# BoxVersion_Taster_v1.net
KiCad netlist of a schematic drawn in EAGLE
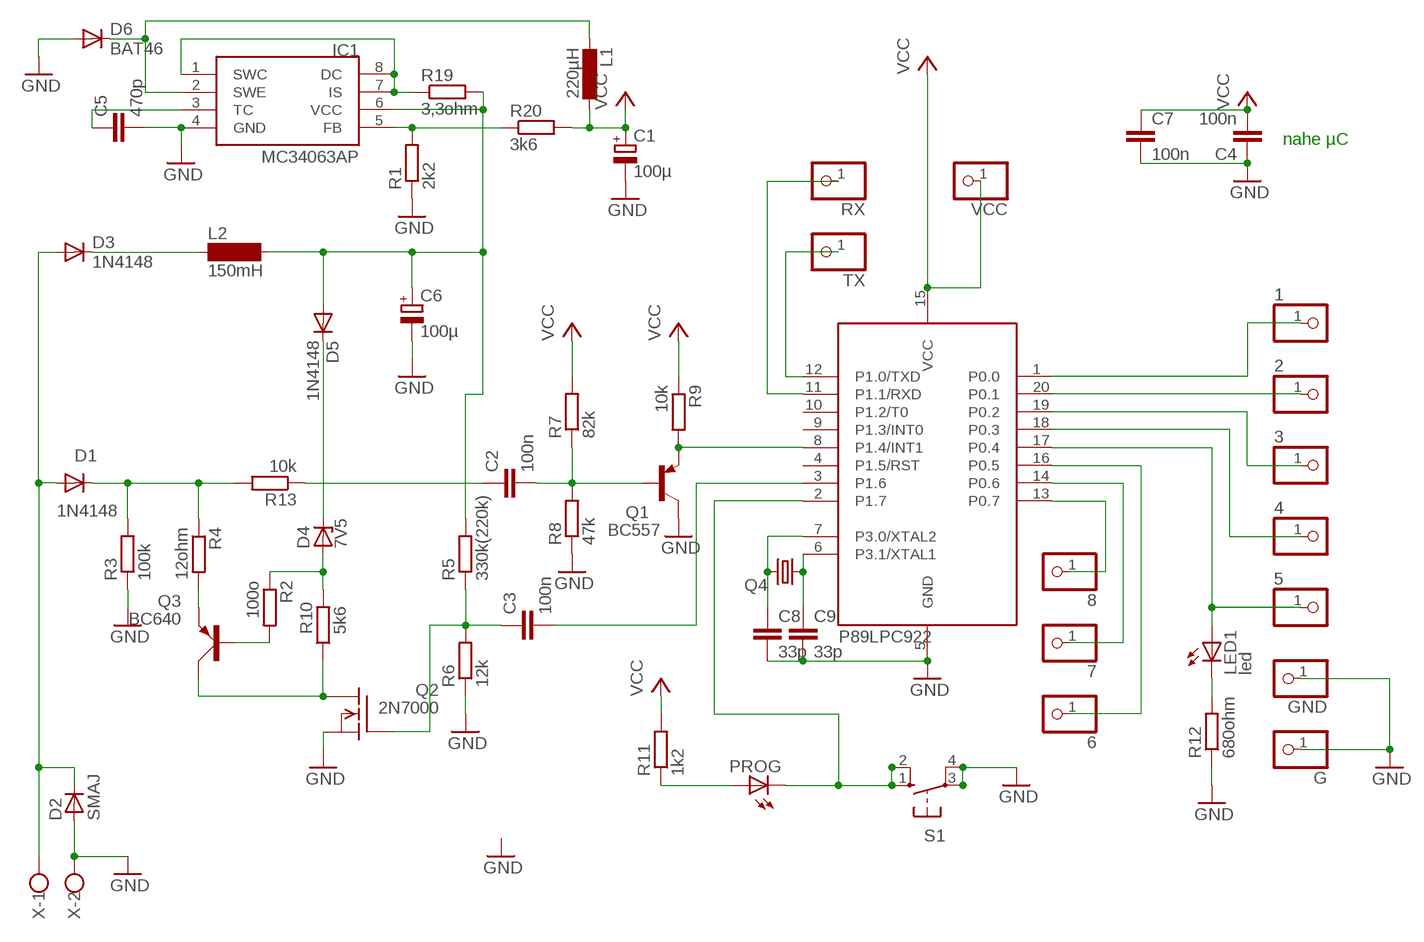
[diagram p0: schematic, sheet 1]

(export (version "E")
  (design (tool "Eeschema 10.0.6"))
  (components
    (comp (ref "1")
      (value "PINHD-1X1")
      (footprint "eagle-import:1X01")
      (libsource (lib "eagle-import") (part "PINHD-1X1"))
    )
    (comp (ref "2")
      (value "PINHD-1X1")
      (footprint "eagle-import:1X01")
      (libsource (lib "eagle-import") (part "PINHD-1X1"))
    )
    (comp (ref "3")
      (value "PINHD-1X1")
      (footprint "eagle-import:1X01")
      (libsource (lib "eagle-import") (part "PINHD-1X1"))
    )
    (comp (ref "4")
      (value "PINHD-1X1")
      (footprint "eagle-import:1X01")
      (libsource (lib "eagle-import") (part "PINHD-1X1"))
    )
    (comp (ref "5")
      (value "PINHD-1X1")
      (footprint "eagle-import:1X01")
      (libsource (lib "eagle-import") (part "PINHD-1X1"))
    )
    (comp (ref "6")
      (value "PINHD-1X1")
      (footprint "eagle-import:1X01")
      (libsource (lib "eagle-import") (part "PINHD-1X1"))
    )
    (comp (ref "7")
      (value "PINHD-1X1")
      (footprint "eagle-import:1X01")
      (libsource (lib "eagle-import") (part "PINHD-1X1"))
    )
    (comp (ref "8")
      (value "PINHD-1X1")
      (footprint "eagle-import:1X01")
      (libsource (lib "eagle-import") (part "PINHD-1X1"))
    )
    (comp (ref "C1")
      (value "100µ")
      (footprint "eagle-import:E5-5")
      (libsource (lib "eagle-import") (part "CPOL-EUE5-5"))
    )
    (comp (ref "C2")
      (value "100n")
      (footprint "eagle-import:C050-024X044")
      (libsource (lib "eagle-import") (part "C-EU050-024X044"))
    )
    (comp (ref "C3")
      (value "100n")
      (footprint "eagle-import:C050-024X044")
      (libsource (lib "eagle-import") (part "C-EU050-024X044"))
    )
    (comp (ref "C4")
      (value "100n")
      (footprint "eagle-import:C050-024X044")
      (libsource (lib "eagle-import") (part "C-EU050-024X044"))
    )
    (comp (ref "C5")
      (value "470p")
      (footprint "eagle-import:C025-024X044")
      (libsource (lib "eagle-import") (part "C-EU025-024X044"))
    )
    (comp (ref "C6")
      (value "100µ")
      (footprint "eagle-import:E5-6")
      (libsource (lib "eagle-import") (part "CPOL-EUE5-6"))
    )
    (comp (ref "C7")
      (value "100n")
      (footprint "eagle-import:C1206")
      (libsource (lib "eagle-import") (part "C-EUC1206"))
    )
    (comp (ref "C8")
      (value "33p")
      (footprint "eagle-import:C1206")
      (libsource (lib "eagle-import") (part "C-EUC1206"))
    )
    (comp (ref "C9")
      (value "33p")
      (footprint "eagle-import:C1206")
      (libsource (lib "eagle-import") (part "C-EUC1206"))
    )
    (comp (ref "D1")
      (value "1N4148")
      (footprint "eagle-import:D-2.5")
      (libsource (lib "eagle-import") (part "1N41481N4148S"))
    )
    (comp (ref "D2")
      (value "SMAJ")
      (footprint "eagle-import:MELF-MLL41")
      (libsource (lib "eagle-import") (part "D-MLL-41"))
    )
    (comp (ref "D3")
      (value "1N4148")
      (footprint "eagle-import:D-2.5")
      (libsource (lib "eagle-import") (part "1N41481N4148S"))
    )
    (comp (ref "D4")
      (value "7V5")
      (footprint "eagle-import:ZDIO-2.5")
      (libsource (lib "eagle-import") (part "ZENER-DIODEZD-2.5"))
    )
    (comp (ref "D5")
      (value "1N4148")
      (footprint "eagle-import:D-2.5")
      (libsource (lib "eagle-import") (part "1N41481N4148S"))
    )
    (comp (ref "D6")
      (value "BAT46")
      (footprint "eagle-import:D-2.5")
      (libsource (lib "eagle-import") (part "DIODE-D-2.5"))
    )
    (comp (ref "G")
      (value "PINHD-1X1")
      (footprint "eagle-import:1X01")
      (libsource (lib "eagle-import") (part "PINHD-1X1"))
    )
    (comp (ref "GND")
      (value "PINHD-1X1")
      (footprint "eagle-import:1X01")
      (libsource (lib "eagle-import") (part "PINHD-1X1"))
    )
    (comp (ref "IC1")
      (value "MC34063AP")
      (footprint "eagle-import:DIL08")
      (libsource (lib "eagle-import") (part "MC34063AP"))
    )
    (comp (ref "L1")
      (value "220µH")
      (footprint "eagle-import:0204_7")
      (libsource (lib "eagle-import") (part "L-EU0204/7"))
    )
    (comp (ref "L2")
      (value "150mH")
      (footprint "eagle-import:SD12K100")
      (libsource (lib "eagle-import") (part "SD12K100"))
    )
    (comp (ref "LED1")
      (value "led")
      (footprint "eagle-import:LZR181")
      (libsource (lib "eagle-import") (part "LEDLZR181"))
    )
    (comp (ref "PROG")
      (value "LEDLZR181")
      (footprint "eagle-import:LZR181")
      (libsource (lib "eagle-import") (part "LEDLZR181"))
    )
    (comp (ref "Q1")
      (value "BC557")
      (footprint "eagle-import:TO92")
      (libsource (lib "eagle-import") (part "BC557"))
    )
    (comp (ref "Q2")
      (value "2N7000")
      (footprint "eagle-import:TO237")
      (libsource (lib "eagle-import") (part "VN2222KM"))
    )
    (comp (ref "Q3")
      (value "BC640")
      (footprint "eagle-import:SOT54D")
      (libsource (lib "eagle-import") (part "BC640"))
    )
    (comp (ref "Q4")
      (value "CRYSTALHC49S")
      (footprint "eagle-import:HC49_S")
      (libsource (lib "eagle-import") (part "CRYSTALHC49S"))
    )
    (comp (ref "R1")
      (value "2k2")
      (footprint "eagle-import:0207_2V")
      (libsource (lib "eagle-import") (part "R-EU_0207/2V"))
    )
    (comp (ref "R2")
      (value "100o")
      (footprint "eagle-import:0207_2V")
      (libsource (lib "eagle-import") (part "R-EU_0207/2V"))
    )
    (comp (ref "R3")
      (value "100k")
      (footprint "eagle-import:0207_2V")
      (libsource (lib "eagle-import") (part "R-EU_0207/2V"))
    )
    (comp (ref "R4")
      (value "12ohm")
      (footprint "eagle-import:0207_2V")
      (libsource (lib "eagle-import") (part "R-EU_0207/2V"))
    )
    (comp (ref "R5")
      (value "330k(220k)")
      (footprint "eagle-import:0207_2V")
      (libsource (lib "eagle-import") (part "R-EU_0207/2V"))
    )
    (comp (ref "R6")
      (value "12k")
      (footprint "eagle-import:0207_2V")
      (libsource (lib "eagle-import") (part "R-EU_0207/2V"))
    )
    (comp (ref "R7")
      (value "82k")
      (footprint "eagle-import:0207_2V")
      (libsource (lib "eagle-import") (part "R-EU_0207/2V"))
    )
    (comp (ref "R8")
      (value "47k")
      (footprint "eagle-import:0204_7")
      (libsource (lib "eagle-import") (part "R-EU_0204/7"))
    )
    (comp (ref "R9")
      (value "10k")
      (footprint "eagle-import:0207_2V")
      (libsource (lib "eagle-import") (part "R-EU_0207/2V"))
    )
    (comp (ref "R10")
      (value "5k6")
      (footprint "eagle-import:0207_2V")
      (libsource (lib "eagle-import") (part "R-EU_0207/2V"))
    )
    (comp (ref "R11")
      (value "1k2")
      (footprint "eagle-import:0207_2V")
      (libsource (lib "eagle-import") (part "R-EU_0207/2V"))
    )
    (comp (ref "R12")
      (value "680ohm")
      (footprint "eagle-import:0204_7")
      (libsource (lib "eagle-import") (part "R-EU_0204/7"))
    )
    (comp (ref "R13")
      (value "10k")
      (footprint "eagle-import:0207_2V")
      (libsource (lib "eagle-import") (part "R-EU_0207/2V"))
    )
    (comp (ref "R19")
      (value "3,3ohm")
      (footprint "eagle-import:0207_2V")
      (libsource (lib "eagle-import") (part "R-EU_0207/2V"))
    )
    (comp (ref "R20")
      (value "3k6")
      (footprint "eagle-import:0207_2V")
      (libsource (lib "eagle-import") (part "R-EU_0207/2V"))
    )
    (comp (ref "RX")
      (value "PINHD-1X1")
      (footprint "eagle-import:1X01")
      (libsource (lib "eagle-import") (part "PINHD-1X1"))
    )
    (comp (ref "S1")
      (value "10-XX")
      (footprint "eagle-import:B3F-10XX")
      (fields (field (name "MPN") "B3F-1000"))
      (libsource (lib "eagle-import") (part "10-XX"))
    )
    (comp (ref "TX")
      (value "PINHD-1X1")
      (footprint "eagle-import:1X01")
      (libsource (lib "eagle-import") (part "PINHD-1X1"))
    )
    (comp (ref "U1")
      (value "89LPC922")
      (footprint "eagle-import:DIL20")
      (libsource (lib "eagle-import") (part "89LPC922"))
    )
    (comp (ref "VCC")
      (value "PINHD-1X1")
      (footprint "eagle-import:1X01")
      (libsource (lib "eagle-import") (part "PINHD-1X1"))
    )
    (comp (ref "X")
      (value "W237-02P")
      (footprint "eagle-import:W237-132")
      (libsource (lib "eagle-import") (part "W237-02P"))
    )
  )
  (nets
    (net (code "1") (name "GND") (class "Default")
      (node (ref "C1") (pin "-") (pinfunction "-_-") (pintype "passive"))
      (node (ref "C4") (pin "1") (pinfunction "1_1") (pintype "passive"))
      (node (ref "C5") (pin "2") (pinfunction "2_2") (pintype "passive"))
      (node (ref "C6") (pin "-") (pinfunction "-_-") (pintype "passive"))
      (node (ref "C7") (pin "2") (pinfunction "2_2") (pintype "passive"))
      (node (ref "C8") (pin "2") (pinfunction "2_2") (pintype "passive"))
      (node (ref "C9") (pin "2") (pinfunction "2_2") (pintype "passive"))
      (node (ref "D2") (pin "2") (pinfunction "A_2") (pintype "passive"))
      (node (ref "D6") (pin "A") (pinfunction "A_A") (pintype "passive"))
      (node (ref "G") (pin "1") (pinfunction "1_1") (pintype "passive"))
      (node (ref "GND") (pin "1") (pinfunction "1_1") (pintype "passive"))
      (node (ref "IC1") (pin "4") (pinfunction "GND_4") (pintype "passive"))
      (node (ref "Q1") (pin "3") (pinfunction "C_3") (pintype "passive"))
      (node (ref "Q2") (pin "3") (pinfunction "S_3") (pintype "passive"))
      (node (ref "R1") (pin "1") (pinfunction "1_1") (pintype "passive"))
      (node (ref "R12") (pin "1") (pinfunction "1_1") (pintype "passive"))
      (node (ref "R3") (pin "1") (pinfunction "1_1") (pintype "passive"))
      (node (ref "R6") (pin "1") (pinfunction "1_1") (pintype "passive"))
      (node (ref "R8") (pin "1") (pinfunction "1_1") (pintype "passive"))
      (node (ref "S1") (pin "3") (pinfunction "P_3") (pintype "passive"))
      (node (ref "S1") (pin "4") (pinfunction "P1_4") (pintype "passive"))
      (node (ref "U1") (pin "5") (pinfunction "GND_5") (pintype "bidirectional"))
      (node (ref "X") (pin "2") (pinfunction "KL_2") (pintype "passive"))
    )
    (net (code "2") (name "Net-(C2-Pad1)") (class "Default")
      (node (ref "C2") (pin "1") (pinfunction "1_1") (pintype "passive"))
      (node (ref "R13") (pin "1") (pinfunction "1_1") (pintype "passive"))
    )
    (net (code "3") (name "Net-(D1-PadC)") (class "Default")
      (node (ref "D1") (pin "C") (pinfunction "C_C") (pintype "passive"))
      (node (ref "R13") (pin "2") (pinfunction "2_2") (pintype "passive"))
      (node (ref "R3") (pin "2") (pinfunction "2_2") (pintype "passive"))
      (node (ref "R4") (pin "1") (pinfunction "1_1") (pintype "passive"))
    )
    (net (code "4") (name "Net-(D2-C)") (class "Default")
      (node (ref "D1") (pin "A") (pinfunction "A_A") (pintype "passive"))
      (node (ref "D2") (pin "1") (pinfunction "C_1") (pintype "passive"))
      (node (ref "D3") (pin "A") (pinfunction "A_A") (pintype "passive"))
      (node (ref "X") (pin "1") (pinfunction "KL_1") (pintype "passive"))
    )
    (net (code "5") (name "Net-(D3-PadC)") (class "Default")
      (node (ref "D3") (pin "C") (pinfunction "C_C") (pintype "passive"))
      (node (ref "L2") (pin "1") (pinfunction "1_1") (pintype "passive"))
    )
    (net (code "6") (name "Net-(D4-PadA)") (class "Default")
      (node (ref "D4") (pin "A") (pinfunction "A_A") (pintype "passive"))
      (node (ref "R10") (pin "2") (pinfunction "2_2") (pintype "passive"))
      (node (ref "R2") (pin "1") (pinfunction "1_1") (pintype "passive"))
    )
    (net (code "7") (name "Net-(D4-PadC)") (class "Default")
      (node (ref "D4") (pin "C") (pinfunction "C_C") (pintype "passive"))
      (node (ref "D5") (pin "C") (pinfunction "C_C") (pintype "passive"))
    )
    (net (code "8") (name "Net-(IC1-DC)") (class "Default")
      (node (ref "IC1") (pin "1") (pinfunction "SWC_1") (pintype "passive"))
      (node (ref "IC1") (pin "7") (pinfunction "IS_7") (pintype "passive"))
      (node (ref "IC1") (pin "8") (pinfunction "DC_8") (pintype "passive"))
      (node (ref "R19") (pin "1") (pinfunction "1_1") (pintype "passive"))
    )
    (net (code "9") (name "Net-(IC1-FB)") (class "Default")
      (node (ref "IC1") (pin "5") (pinfunction "FB_5") (pintype "passive"))
      (node (ref "R1") (pin "2") (pinfunction "2_2") (pintype "passive"))
      (node (ref "R20") (pin "1") (pinfunction "1_1") (pintype "passive"))
    )
    (net (code "10") (name "Net-(IC1-SWE)") (class "Default")
      (node (ref "D6") (pin "C") (pinfunction "C_C") (pintype "passive"))
      (node (ref "IC1") (pin "2") (pinfunction "SWE_2") (pintype "passive"))
      (node (ref "L1") (pin "2") (pinfunction "2_2") (pintype "passive"))
    )
    (net (code "11") (name "Net-(IC1-TC)") (class "Default")
      (node (ref "C5") (pin "1") (pinfunction "1_1") (pintype "passive"))
      (node (ref "IC1") (pin "3") (pinfunction "TC_3") (pintype "passive"))
    )
    (net (code "12") (name "Net-(IC1-VCC)") (class "Default")
      (node (ref "C6") (pin "+") (pinfunction "+_+") (pintype "passive"))
      (node (ref "D5") (pin "A") (pinfunction "A_A") (pintype "passive"))
      (node (ref "IC1") (pin "6") (pinfunction "VCC_6") (pintype "passive"))
      (node (ref "L2") (pin "2") (pinfunction "2_2") (pintype "passive"))
      (node (ref "R19") (pin "2") (pinfunction "2_2") (pintype "passive"))
      (node (ref "R5") (pin "2") (pinfunction "2_2") (pintype "passive"))
    )
    (net (code "13") (name "Net-(LED1-C)") (class "Default")
      (node (ref "LED1") (pin "K") (pinfunction "C_K") (pintype "passive"))
      (node (ref "R12") (pin "2") (pinfunction "2_2") (pintype "passive"))
    )
    (net (code "14") (name "Net-(PROG-C)") (class "Default")
      (node (ref "PROG") (pin "K") (pinfunction "C_K") (pintype "passive"))
      (node (ref "S1") (pin "1") (pinfunction "S_1") (pintype "passive"))
      (node (ref "S1") (pin "2") (pinfunction "S1_2") (pintype "passive"))
      (node (ref "U1") (pin "2") (pinfunction "P1.7_2") (pintype "bidirectional"))
    )
    (net (code "15") (name "Net-(PROG-PadA)") (class "Default")
      (node (ref "PROG") (pin "A") (pinfunction "A_A") (pintype "passive"))
      (node (ref "R11") (pin "1") (pinfunction "1_1") (pintype "passive"))
    )
    (net (code "16") (name "Net-(Q1-B)") (class "Default")
      (node (ref "C2") (pin "2") (pinfunction "2_2") (pintype "passive"))
      (node (ref "Q1") (pin "2") (pinfunction "B_2") (pintype "passive"))
      (node (ref "R7") (pin "1") (pinfunction "1_1") (pintype "passive"))
      (node (ref "R8") (pin "2") (pinfunction "2_2") (pintype "passive"))
    )
    (net (code "17") (name "Net-(Q1-E)") (class "Default")
      (node (ref "Q1") (pin "1") (pinfunction "E_1") (pintype "passive"))
      (node (ref "R9") (pin "2") (pinfunction "2_2") (pintype "passive"))
      (node (ref "U1") (pin "8") (pinfunction "P1.4/INT1_8") (pintype "bidirectional"))
    )
    (net (code "18") (name "Net-(Q2-D)") (class "Default")
      (node (ref "Q2") (pin "1") (pinfunction "D_1") (pintype "passive"))
      (node (ref "Q3") (pin "C") (pinfunction "C_C") (pintype "passive"))
      (node (ref "R10") (pin "1") (pinfunction "1_1") (pintype "passive"))
    )
    (net (code "19") (name "Net-(Q2-G)") (class "Default")
      (node (ref "C3") (pin "1") (pinfunction "1_1") (pintype "passive"))
      (node (ref "Q2") (pin "2") (pinfunction "G_2") (pintype "passive"))
      (node (ref "R5") (pin "1") (pinfunction "1_1") (pintype "passive"))
      (node (ref "R6") (pin "2") (pinfunction "2_2") (pintype "passive"))
    )
    (net (code "20") (name "Net-(Q3-PadB)") (class "Default")
      (node (ref "Q3") (pin "B") (pinfunction "B_B") (pintype "passive"))
      (node (ref "R2") (pin "2") (pinfunction "2_2") (pintype "passive"))
    )
    (net (code "21") (name "Net-(Q3-PadE)") (class "Default")
      (node (ref "Q3") (pin "E") (pinfunction "E_E") (pintype "passive"))
      (node (ref "R4") (pin "2") (pinfunction "2_2") (pintype "passive"))
    )
    (net (code "22") (name "Net-(U1-P0.0)") (class "Default")
      (node (ref "1") (pin "1") (pinfunction "1_1") (pintype "passive"))
      (node (ref "U1") (pin "1") (pinfunction "P0.0_1") (pintype "bidirectional"))
    )
    (net (code "23") (name "Net-(U1-P0.1)") (class "Default")
      (node (ref "2") (pin "1") (pinfunction "1_1") (pintype "passive"))
      (node (ref "U1") (pin "20") (pinfunction "P0.1_20") (pintype "bidirectional"))
    )
    (net (code "24") (name "Net-(U1-P0.2)") (class "Default")
      (node (ref "3") (pin "1") (pinfunction "1_1") (pintype "passive"))
      (node (ref "U1") (pin "19") (pinfunction "P0.2_19") (pintype "bidirectional"))
    )
    (net (code "25") (name "Net-(U1-P0.3)") (class "Default")
      (node (ref "4") (pin "1") (pinfunction "1_1") (pintype "passive"))
      (node (ref "U1") (pin "18") (pinfunction "P0.3_18") (pintype "bidirectional"))
    )
    (net (code "26") (name "Net-(U1-P0.4)") (class "Default")
      (node (ref "5") (pin "1") (pinfunction "1_1") (pintype "passive"))
      (node (ref "LED1") (pin "A") (pinfunction "A_A") (pintype "passive"))
      (node (ref "U1") (pin "17") (pinfunction "P0.4_17") (pintype "bidirectional"))
    )
    (net (code "27") (name "Net-(U1-P0.5)") (class "Default")
      (node (ref "6") (pin "1") (pinfunction "1_1") (pintype "passive"))
      (node (ref "U1") (pin "16") (pinfunction "P0.5_16") (pintype "bidirectional"))
    )
    (net (code "28") (name "Net-(U1-P0.6)") (class "Default")
      (node (ref "7") (pin "1") (pinfunction "1_1") (pintype "passive"))
      (node (ref "U1") (pin "14") (pinfunction "P0.6_14") (pintype "bidirectional"))
    )
    (net (code "29") (name "Net-(U1-P0.7)") (class "Default")
      (node (ref "8") (pin "1") (pinfunction "1_1") (pintype "passive"))
      (node (ref "U1") (pin "13") (pinfunction "P0.7_13") (pintype "bidirectional"))
    )
    (net (code "30") (name "Net-(U1-P1.0{slash}TXD)") (class "Default")
      (node (ref "TX") (pin "1") (pinfunction "1_1") (pintype "passive"))
      (node (ref "U1") (pin "12") (pinfunction "P1.0/TXD_12") (pintype "bidirectional"))
    )
    (net (code "31") (name "Net-(U1-P1.1{slash}RXD)") (class "Default")
      (node (ref "RX") (pin "1") (pinfunction "1_1") (pintype "passive"))
      (node (ref "U1") (pin "11") (pinfunction "P1.1/RXD_11") (pintype "bidirectional"))
    )
    (net (code "32") (name "Net-(U1-P1.6)") (class "Default")
      (node (ref "C3") (pin "2") (pinfunction "2_2") (pintype "passive"))
      (node (ref "U1") (pin "3") (pinfunction "P1.6_3") (pintype "bidirectional"))
    )
    (net (code "33") (name "Net-(U1-P3.0{slash}XTAL2)") (class "Default")
      (node (ref "C8") (pin "1") (pinfunction "1_1") (pintype "passive"))
      (node (ref "Q4") (pin "2") (pinfunction "2_2") (pintype "passive"))
      (node (ref "U1") (pin "7") (pinfunction "P3.0/XTAL2_7") (pintype "bidirectional"))
    )
    (net (code "34") (name "Net-(U1-P3.1{slash}XTAL1)") (class "Default")
      (node (ref "C9") (pin "1") (pinfunction "1_1") (pintype "passive"))
      (node (ref "Q4") (pin "1") (pinfunction "1_1") (pintype "passive"))
      (node (ref "U1") (pin "6") (pinfunction "P3.1/XTAL1_6") (pintype "bidirectional"))
    )
    (net (code "35") (name "VCC") (class "Default")
      (node (ref "C1") (pin "+") (pinfunction "+_+") (pintype "passive"))
      (node (ref "C4") (pin "2") (pinfunction "2_2") (pintype "passive"))
      (node (ref "C7") (pin "1") (pinfunction "1_1") (pintype "passive"))
      (node (ref "L1") (pin "1") (pinfunction "1_1") (pintype "passive"))
      (node (ref "R11") (pin "2") (pinfunction "2_2") (pintype "passive"))
      (node (ref "R20") (pin "2") (pinfunction "2_2") (pintype "passive"))
      (node (ref "R7") (pin "2") (pinfunction "2_2") (pintype "passive"))
      (node (ref "R9") (pin "1") (pinfunction "1_1") (pintype "passive"))
      (node (ref "U1") (pin "15") (pinfunction "VCC_15") (pintype "bidirectional"))
      (node (ref "VCC") (pin "1") (pinfunction "1_1") (pintype "passive"))
    )
    (net (code "36") (name "unconnected-(U1-P1.2{slash}T0-Pad10)") (class "Default")
      (node (ref "U1") (pin "10") (pinfunction "P1.2/T0_10") (pintype "bidirectional"))
    )
    (net (code "37") (name "unconnected-(U1-P1.3{slash}INT0-Pad9)") (class "Default")
      (node (ref "U1") (pin "9") (pinfunction "P1.3/INT0_9") (pintype "bidirectional"))
    )
    (net (code "38") (name "unconnected-(U1-P1.5{slash}RST-Pad4)") (class "Default")
      (node (ref "U1") (pin "4") (pinfunction "P1.5/RST_4") (pintype "bidirectional"))
    )
  )
)
